# brd_esp32.net
KiCad netlist of a schematic drawn in EAGLE
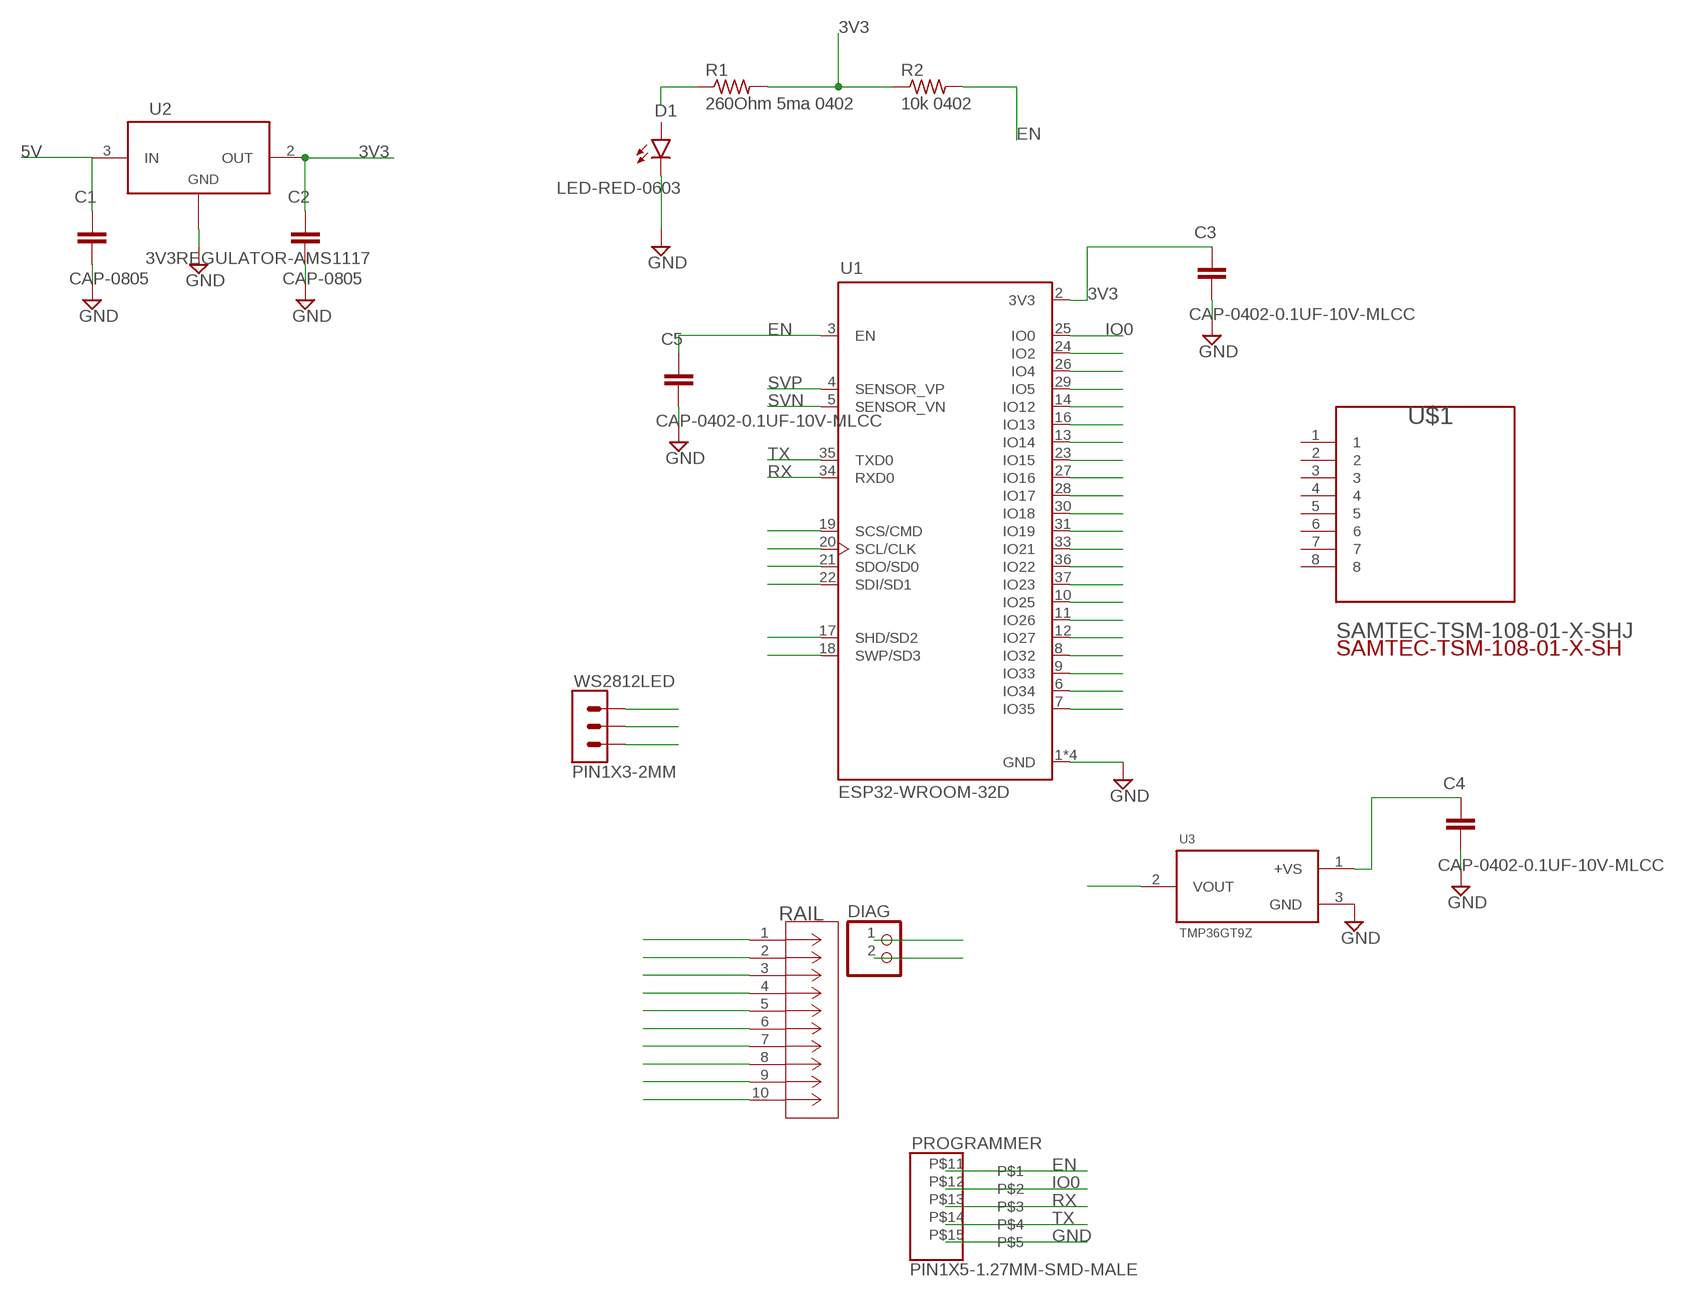
[diagram p0: schematic, sheet 1]

(export (version "E")
  (design (tool "Eeschema 10.0.6"))
  (components
    (comp (ref "C1")
      (value "CAP-0805")
      (footprint "eagle-import:CAP_0805")
      (fields
        (field (name "DIGIKEY_PART_NUMBER") "311-1140-2-ND")
        (field (name "MANUFACTURER") "Yageo")
        (field (name "MPN") "CC0805KRX7R9BB104")
        (field (name "CREATED_BY") "PCBLayout.com")
      )
      (libsource (lib "eagle-import") (part "CAP-0805"))
    )
    (comp (ref "C2")
      (value "CAP-0805")
      (footprint "eagle-import:CAP_0805")
      (fields
        (field (name "DIGIKEY_PART_NUMBER") "311-1140-2-ND")
        (field (name "MANUFACTURER") "Yageo")
        (field (name "MPN") "CC0805KRX7R9BB104")
        (field (name "CREATED_BY") "PCBLayout.com")
      )
      (libsource (lib "eagle-import") (part "CAP-0805"))
    )
    (comp (ref "C3")
      (value "CAP-0402-0.1UF-10V-MLCC")
      (footprint "eagle-import:CAP_0402")
      (fields
        (field (name "DIGIKEY_PART_NUMBER") "VJ0402G104KXQCW1BC")
        (field (name "MANUFACTURER") " Vishay Intertech")
        (field (name "CREATED_BY") "ChiliPeppr")
      )
      (libsource (lib "eagle-import") (part "CAP-0402-0.1UF-10V-MLCC"))
    )
    (comp (ref "C4")
      (value "CAP-0402-0.1UF-10V-MLCC")
      (footprint "eagle-import:CAP_0402")
      (fields
        (field (name "DIGIKEY_PART_NUMBER") "VJ0402G104KXQCW1BC")
        (field (name "MANUFACTURER") " Vishay Intertech")
        (field (name "CREATED_BY") "ChiliPeppr")
      )
      (libsource (lib "eagle-import") (part "CAP-0402-0.1UF-10V-MLCC"))
    )
    (comp (ref "C5")
      (value "CAP-0402-0.1UF-10V-MLCC")
      (footprint "eagle-import:CAP_0402")
      (fields
        (field (name "DIGIKEY_PART_NUMBER") "VJ0402G104KXQCW1BC")
        (field (name "MANUFACTURER") " Vishay Intertech")
        (field (name "CREATED_BY") "ChiliPeppr")
      )
      (libsource (lib "eagle-import") (part "CAP-0402-0.1UF-10V-MLCC"))
    )
    (comp (ref "D1")
      (value "LED-RED-0603")
      (footprint "eagle-import:LED-0603")
      (fields
        (field (name "DIGIKEY_PART_NUMBER") " FC-DA1608HRK-620D")
        (field (name "MANUFACTURER") "Foshan NationStar Optoelectronics")
        (field (name "MPN") "FC-DA1608HRK-620D")
        (field (name "CREATED_BY") "ChiliPeppr")
      )
      (libsource (lib "eagle-import") (part "LED-RED-0603"))
    )
    (comp (ref "DIAG")
      (value "PINHD-1X2")
      (footprint "eagle-import:1X02")
      (libsource (lib "eagle-import") (part "PINHD-1X2"))
    )
    (comp (ref "PROGRAMMER")
      (value "PIN1X5-1.27MM-SMD-MALE")
      (footprint "eagle-import:PIN1X5-1.27MM-SMD")
      (libsource (lib "eagle-import") (part "PIN1X5-1.27MM-SMD-MALE"))
    )
    (comp (ref "R1")
      (value "260Ohm 5ma 0402")
      (footprint "eagle-import:RES_0402")
      (fields (field (name "CREATED_BY") "ChiliPeppr"))
      (libsource (lib "eagle-import") (part "RES-0402"))
    )
    (comp (ref "R2")
      (value "10k 0402")
      (footprint "eagle-import:RES_0402")
      (fields (field (name "CREATED_BY") "ChiliPeppr"))
      (libsource (lib "eagle-import") (part "RES-0402"))
    )
    (comp (ref "RAIL")
      (value "SSW-105-01-G-D")
      (footprint "eagle-import:CON10_2X5_TU_SSQ")
      (fields (field (name "MANUFACTURER_PART_NUMBER") "SSW10501GD"))
      (libsource (lib "eagle-import") (part "SSW-105-01-G-D"))
    )
    (comp (ref "U$1")
      (value "SAMTEC-TSM-108-01-X-SHJ")
      (footprint "eagle-import:SAMTEC-TSM-108-01-X-SH")
      (fields
        (field (name "DIGI-KEY_PART_NUMBER") "SAM10294-ND")
        (field (name "MF") "Samtec Inc.")
        (field (name "MP") "TSM-108-01-L-SH")
      )
      (libsource (lib "eagle-import") (part "SAMTEC-TSM-108-01-X-SHJ"))
    )
    (comp (ref "U1")
      (value "ESP32-WROOM-32D")
      (footprint "eagle-import:MODULE_ESP32-WROOM-32D")
      (fields (field (name "DIGI-KEY_PART_NUMBER") "1904-1023-1-ND") (field (name "MF") "Espressif Systems"))
      (libsource (lib "eagle-import") (part "ESP32-WROOM-32D"))
    )
    (comp (ref "U2")
      (value "3V3REGULATOR-AMS1117")
      (footprint "eagle-import:SOT-223")
      (fields
        (field (name "DIGIKEY_PART_NUMBER") "NCP1117ST33T3GOSTR-ND")
        (field (name "MANUFACTURER") "ON Semiconductor")
        (field (name "MPN") "NCP1117ST33T3G")
        (field (name "CREATED_BY") "PCBLayout.com")
      )
      (libsource (lib "eagle-import") (part "3V3REGULATOR-AMS1117"))
    )
    (comp (ref "U3")
      (value "TMP36GT9Z")
      (footprint "eagle-import:TO127P419X483X533-3P")
      (fields (field (name "MF") "Analog Devices"))
      (libsource (lib "eagle-import") (part "TMP36GT9Z"))
    )
    (comp (ref "WS2812LED")
      (value "PIN1X3-2MM")
      (footprint "eagle-import:PIN1X3-2MM")
      (fields
        (field (name "MANUFACTURER") " Würth Elektronik ")
        (field (name "MPN") "62000311121")
        (field (name "CREATED_BY") "PCBLayout.com")
      )
      (libsource (lib "eagle-import") (part "PIN1X3-2MM"))
    )
  )
  (nets
    (net (code "1") (name "/3V3") (class "Default")
      (node (ref "C2") (pin "1") (pinfunction "1_1") (pintype "passive"))
      (node (ref "C3") (pin "1") (pinfunction "1_1") (pintype "passive"))
      (node (ref "R1") (pin "2") (pinfunction "2_2") (pintype "passive"))
      (node (ref "R2") (pin "1") (pinfunction "1_1") (pintype "passive"))
      (node (ref "U1") (pin "2") (pinfunction "3V3_2") (pintype "power_in"))
      (node (ref "U2") (pin "2") (pinfunction "OUT_2") (pintype "output"))
      (node (ref "U2") (pin "4") (pinfunction "4_4") (pintype "passive"))
    )
    (net (code "2") (name "/5V") (class "Default")
      (node (ref "C1") (pin "1") (pinfunction "1_1") (pintype "passive"))
      (node (ref "U2") (pin "3") (pinfunction "IN_3") (pintype "input"))
    )
    (net (code "3") (name "/EN") (class "Default")
      (node (ref "C5") (pin "1") (pinfunction "1_1") (pintype "passive"))
      (node (ref "PROGRAMMER") (pin "P$11") (pinfunction "P$1_P$11") (pintype "bidirectional"))
      (node (ref "R2") (pin "2") (pinfunction "2_2") (pintype "passive"))
      (node (ref "U1") (pin "3") (pinfunction "EN_3") (pintype "input"))
    )
    (net (code "4") (name "/IO0") (class "Default")
      (node (ref "PROGRAMMER") (pin "P$12") (pinfunction "P$2_P$12") (pintype "bidirectional"))
      (node (ref "U1") (pin "25") (pinfunction "IO0_25") (pintype "bidirectional"))
    )
    (net (code "5") (name "/RX") (class "Default")
      (node (ref "PROGRAMMER") (pin "P$13") (pinfunction "P$3_P$13") (pintype "bidirectional"))
      (node (ref "U1") (pin "34") (pinfunction "RXD0_34") (pintype "bidirectional"))
    )
    (net (code "6") (name "/SVN") (class "Default")
      (node (ref "U1") (pin "5") (pinfunction "SENSOR_VN_5") (pintype "input"))
    )
    (net (code "7") (name "/SVP") (class "Default")
      (node (ref "U1") (pin "4") (pinfunction "SENSOR_VP_4") (pintype "input"))
    )
    (net (code "8") (name "/TX") (class "Default")
      (node (ref "PROGRAMMER") (pin "P$14") (pinfunction "P$4_P$14") (pintype "bidirectional"))
      (node (ref "U1") (pin "35") (pinfunction "TXD0_35") (pintype "bidirectional"))
    )
    (net (code "9") (name "GND") (class "Default")
      (node (ref "C1") (pin "2") (pinfunction "2_2") (pintype "passive"))
      (node (ref "C2") (pin "2") (pinfunction "2_2") (pintype "passive"))
      (node (ref "C3") (pin "2") (pinfunction "2_2") (pintype "passive"))
      (node (ref "C4") (pin "2") (pinfunction "2_2") (pintype "passive"))
      (node (ref "C5") (pin "2") (pinfunction "2_2") (pintype "passive"))
      (node (ref "D1") (pin "C") (pinfunction "C_C") (pintype "passive"))
      (node (ref "PROGRAMMER") (pin "P$15") (pinfunction "P$5_P$15") (pintype "bidirectional"))
      (node (ref "U1") (pin "1") (pinfunction "GND_1") (pintype "power_in"))
      (node (ref "U1") (pin "15") (pinfunction "GND_15") (pintype "power_in"))
      (node (ref "U1") (pin "38") (pinfunction "GND_38") (pintype "power_in"))
      (node (ref "U1") (pin "39") (pinfunction "GND_39") (pintype "power_in"))
      (node (ref "U2") (pin "1") (pinfunction "ADJ/GND_1") (pintype "power_in"))
      (node (ref "U3") (pin "3") (pinfunction "GND_3") (pintype "power_in"))
    )
    (net (code "10") (name "Net-(U3-+VS)") (class "Default")
      (node (ref "C4") (pin "1") (pinfunction "1_1") (pintype "passive"))
      (node (ref "U3") (pin "1") (pinfunction "+VS_1") (pintype "power_in"))
    )
    (net (code "11") (name "unconnected-(D1-PadA)") (class "Default")
      (node (ref "D1") (pin "A") (pinfunction "A_A") (pintype "passive"))
    )
    (net (code "12") (name "unconnected-(DIAG-Pad1)") (class "Default")
      (node (ref "DIAG") (pin "1") (pinfunction "1_1") (pintype "passive"))
    )
    (net (code "13") (name "unconnected-(DIAG-Pad2)") (class "Default")
      (node (ref "DIAG") (pin "2") (pinfunction "2_2") (pintype "passive"))
    )
    (net (code "14") (name "unconnected-(R1-Pad1)") (class "Default")
      (node (ref "R1") (pin "1") (pinfunction "1_1") (pintype "passive"))
    )
    (net (code "15") (name "unconnected-(RAIL-Pad1)") (class "Default")
      (node (ref "RAIL") (pin "1") (pinfunction "1_1") (pintype "passive"))
    )
    (net (code "16") (name "unconnected-(RAIL-Pad2)") (class "Default")
      (node (ref "RAIL") (pin "2") (pinfunction "2_2") (pintype "passive"))
    )
    (net (code "17") (name "unconnected-(RAIL-Pad3)") (class "Default")
      (node (ref "RAIL") (pin "3") (pinfunction "3_3") (pintype "passive"))
    )
    (net (code "18") (name "unconnected-(RAIL-Pad4)") (class "Default")
      (node (ref "RAIL") (pin "4") (pinfunction "4_4") (pintype "passive"))
    )
    (net (code "19") (name "unconnected-(RAIL-Pad5)") (class "Default")
      (node (ref "RAIL") (pin "5") (pinfunction "5_5") (pintype "passive"))
    )
    (net (code "20") (name "unconnected-(RAIL-Pad6)") (class "Default")
      (node (ref "RAIL") (pin "6") (pinfunction "6_6") (pintype "passive"))
    )
    (net (code "21") (name "unconnected-(RAIL-Pad7)") (class "Default")
      (node (ref "RAIL") (pin "7") (pinfunction "7_7") (pintype "passive"))
    )
    (net (code "22") (name "unconnected-(RAIL-Pad8)") (class "Default")
      (node (ref "RAIL") (pin "8") (pinfunction "8_8") (pintype "passive"))
    )
    (net (code "23") (name "unconnected-(RAIL-Pad9)") (class "Default")
      (node (ref "RAIL") (pin "9") (pinfunction "9_9") (pintype "passive"))
    )
    (net (code "24") (name "unconnected-(RAIL-Pad10)") (class "Default")
      (node (ref "RAIL") (pin "10") (pinfunction "10_10") (pintype "passive"))
    )
    (net (code "25") (name "unconnected-(U$1-Pad1)") (class "Default")
      (node (ref "U$1") (pin "1") (pinfunction "1_1") (pintype "bidirectional"))
    )
    (net (code "26") (name "unconnected-(U$1-Pad2)") (class "Default")
      (node (ref "U$1") (pin "2") (pinfunction "2_2") (pintype "bidirectional"))
    )
    (net (code "27") (name "unconnected-(U$1-Pad3)") (class "Default")
      (node (ref "U$1") (pin "3") (pinfunction "3_3") (pintype "bidirectional"))
    )
    (net (code "28") (name "unconnected-(U$1-Pad4)") (class "Default")
      (node (ref "U$1") (pin "4") (pinfunction "4_4") (pintype "bidirectional"))
    )
    (net (code "29") (name "unconnected-(U$1-Pad5)") (class "Default")
      (node (ref "U$1") (pin "5") (pinfunction "5_5") (pintype "bidirectional"))
    )
    (net (code "30") (name "unconnected-(U$1-Pad6)") (class "Default")
      (node (ref "U$1") (pin "6") (pinfunction "6_6") (pintype "bidirectional"))
    )
    (net (code "31") (name "unconnected-(U$1-Pad7)") (class "Default")
      (node (ref "U$1") (pin "7") (pinfunction "7_7") (pintype "bidirectional"))
    )
    (net (code "32") (name "unconnected-(U$1-Pad8)") (class "Default")
      (node (ref "U$1") (pin "8") (pinfunction "8_8") (pintype "bidirectional"))
    )
    (net (code "33") (name "unconnected-(U1-IO2-Pad24)") (class "Default")
      (node (ref "U1") (pin "24") (pinfunction "IO2_24") (pintype "bidirectional"))
    )
    (net (code "34") (name "unconnected-(U1-IO4-Pad26)") (class "Default")
      (node (ref "U1") (pin "26") (pinfunction "IO4_26") (pintype "bidirectional"))
    )
    (net (code "35") (name "unconnected-(U1-IO5-Pad29)") (class "Default")
      (node (ref "U1") (pin "29") (pinfunction "IO5_29") (pintype "bidirectional"))
    )
    (net (code "36") (name "unconnected-(U1-IO12-Pad14)") (class "Default")
      (node (ref "U1") (pin "14") (pinfunction "IO12_14") (pintype "bidirectional"))
    )
    (net (code "37") (name "unconnected-(U1-IO13-Pad16)") (class "Default")
      (node (ref "U1") (pin "16") (pinfunction "IO13_16") (pintype "bidirectional"))
    )
    (net (code "38") (name "unconnected-(U1-IO14-Pad13)") (class "Default")
      (node (ref "U1") (pin "13") (pinfunction "IO14_13") (pintype "bidirectional"))
    )
    (net (code "39") (name "unconnected-(U1-IO15-Pad23)") (class "Default")
      (node (ref "U1") (pin "23") (pinfunction "IO15_23") (pintype "bidirectional"))
    )
    (net (code "40") (name "unconnected-(U1-IO16-Pad27)") (class "Default")
      (node (ref "U1") (pin "27") (pinfunction "IO16_27") (pintype "bidirectional"))
    )
    (net (code "41") (name "unconnected-(U1-IO17-Pad28)") (class "Default")
      (node (ref "U1") (pin "28") (pinfunction "IO17_28") (pintype "bidirectional"))
    )
    (net (code "42") (name "unconnected-(U1-IO18-Pad30)") (class "Default")
      (node (ref "U1") (pin "30") (pinfunction "IO18_30") (pintype "bidirectional"))
    )
    (net (code "43") (name "unconnected-(U1-IO19-Pad31)") (class "Default")
      (node (ref "U1") (pin "31") (pinfunction "IO19_31") (pintype "bidirectional"))
    )
    (net (code "44") (name "unconnected-(U1-IO21-Pad33)") (class "Default")
      (node (ref "U1") (pin "33") (pinfunction "IO21_33") (pintype "bidirectional"))
    )
    (net (code "45") (name "unconnected-(U1-IO22-Pad36)") (class "Default")
      (node (ref "U1") (pin "36") (pinfunction "IO22_36") (pintype "bidirectional"))
    )
    (net (code "46") (name "unconnected-(U1-IO23-Pad37)") (class "Default")
      (node (ref "U1") (pin "37") (pinfunction "IO23_37") (pintype "bidirectional"))
    )
    (net (code "47") (name "unconnected-(U1-IO25-Pad10)") (class "Default")
      (node (ref "U1") (pin "10") (pinfunction "IO25_10") (pintype "bidirectional"))
    )
    (net (code "48") (name "unconnected-(U1-IO26-Pad11)") (class "Default")
      (node (ref "U1") (pin "11") (pinfunction "IO26_11") (pintype "bidirectional"))
    )
    (net (code "49") (name "unconnected-(U1-IO27-Pad12)") (class "Default")
      (node (ref "U1") (pin "12") (pinfunction "IO27_12") (pintype "bidirectional"))
    )
    (net (code "50") (name "unconnected-(U1-IO32-Pad8)") (class "Default")
      (node (ref "U1") (pin "8") (pinfunction "IO32_8") (pintype "bidirectional"))
    )
    (net (code "51") (name "unconnected-(U1-IO33-Pad9)") (class "Default")
      (node (ref "U1") (pin "9") (pinfunction "IO33_9") (pintype "bidirectional"))
    )
    (net (code "52") (name "unconnected-(U1-IO34-Pad6)") (class "Default")
      (node (ref "U1") (pin "6") (pinfunction "IO34_6") (pintype "bidirectional"))
    )
    (net (code "53") (name "unconnected-(U1-IO35-Pad7)") (class "Default")
      (node (ref "U1") (pin "7") (pinfunction "IO35_7") (pintype "bidirectional"))
    )
    (net (code "54") (name "unconnected-(U1-SCL{slash}CLK-Pad20)") (class "Default")
      (node (ref "U1") (pin "20") (pinfunction "SCL/CLK_20") (pintype "bidirectional"))
    )
    (net (code "55") (name "unconnected-(U1-SCS{slash}CMD-Pad19)") (class "Default")
      (node (ref "U1") (pin "19") (pinfunction "SCS/CMD_19") (pintype "bidirectional"))
    )
    (net (code "56") (name "unconnected-(U1-SDI{slash}SD1-Pad22)") (class "Default")
      (node (ref "U1") (pin "22") (pinfunction "SDI/SD1_22") (pintype "bidirectional"))
    )
    (net (code "57") (name "unconnected-(U1-SDO{slash}SD0-Pad21)") (class "Default")
      (node (ref "U1") (pin "21") (pinfunction "SDO/SD0_21") (pintype "bidirectional"))
    )
    (net (code "58") (name "unconnected-(U1-SHD{slash}SD2-Pad17)") (class "Default")
      (node (ref "U1") (pin "17") (pinfunction "SHD/SD2_17") (pintype "bidirectional"))
    )
    (net (code "59") (name "unconnected-(U1-SWP{slash}SD3-Pad18)") (class "Default")
      (node (ref "U1") (pin "18") (pinfunction "SWP/SD3_18") (pintype "bidirectional"))
    )
    (net (code "60") (name "unconnected-(U3-VOUT-Pad2)") (class "Default")
      (node (ref "U3") (pin "2") (pinfunction "VOUT_2") (pintype "output"))
    )
    (net (code "61") (name "unconnected-(WS2812LED-Pad1)") (class "Default")
      (node (ref "WS2812LED") (pin "1") (pinfunction "1_1") (pintype "passive"))
    )
    (net (code "62") (name "unconnected-(WS2812LED-Pad2)") (class "Default")
      (node (ref "WS2812LED") (pin "2") (pinfunction "2_2") (pintype "passive"))
    )
    (net (code "63") (name "unconnected-(WS2812LED-Pad3)") (class "Default")
      (node (ref "WS2812LED") (pin "3") (pinfunction "3_3") (pintype "passive"))
    )
  )
)
